# button-led-matrix-4x4.net
KiCad netlist of a schematic drawn in EAGLE
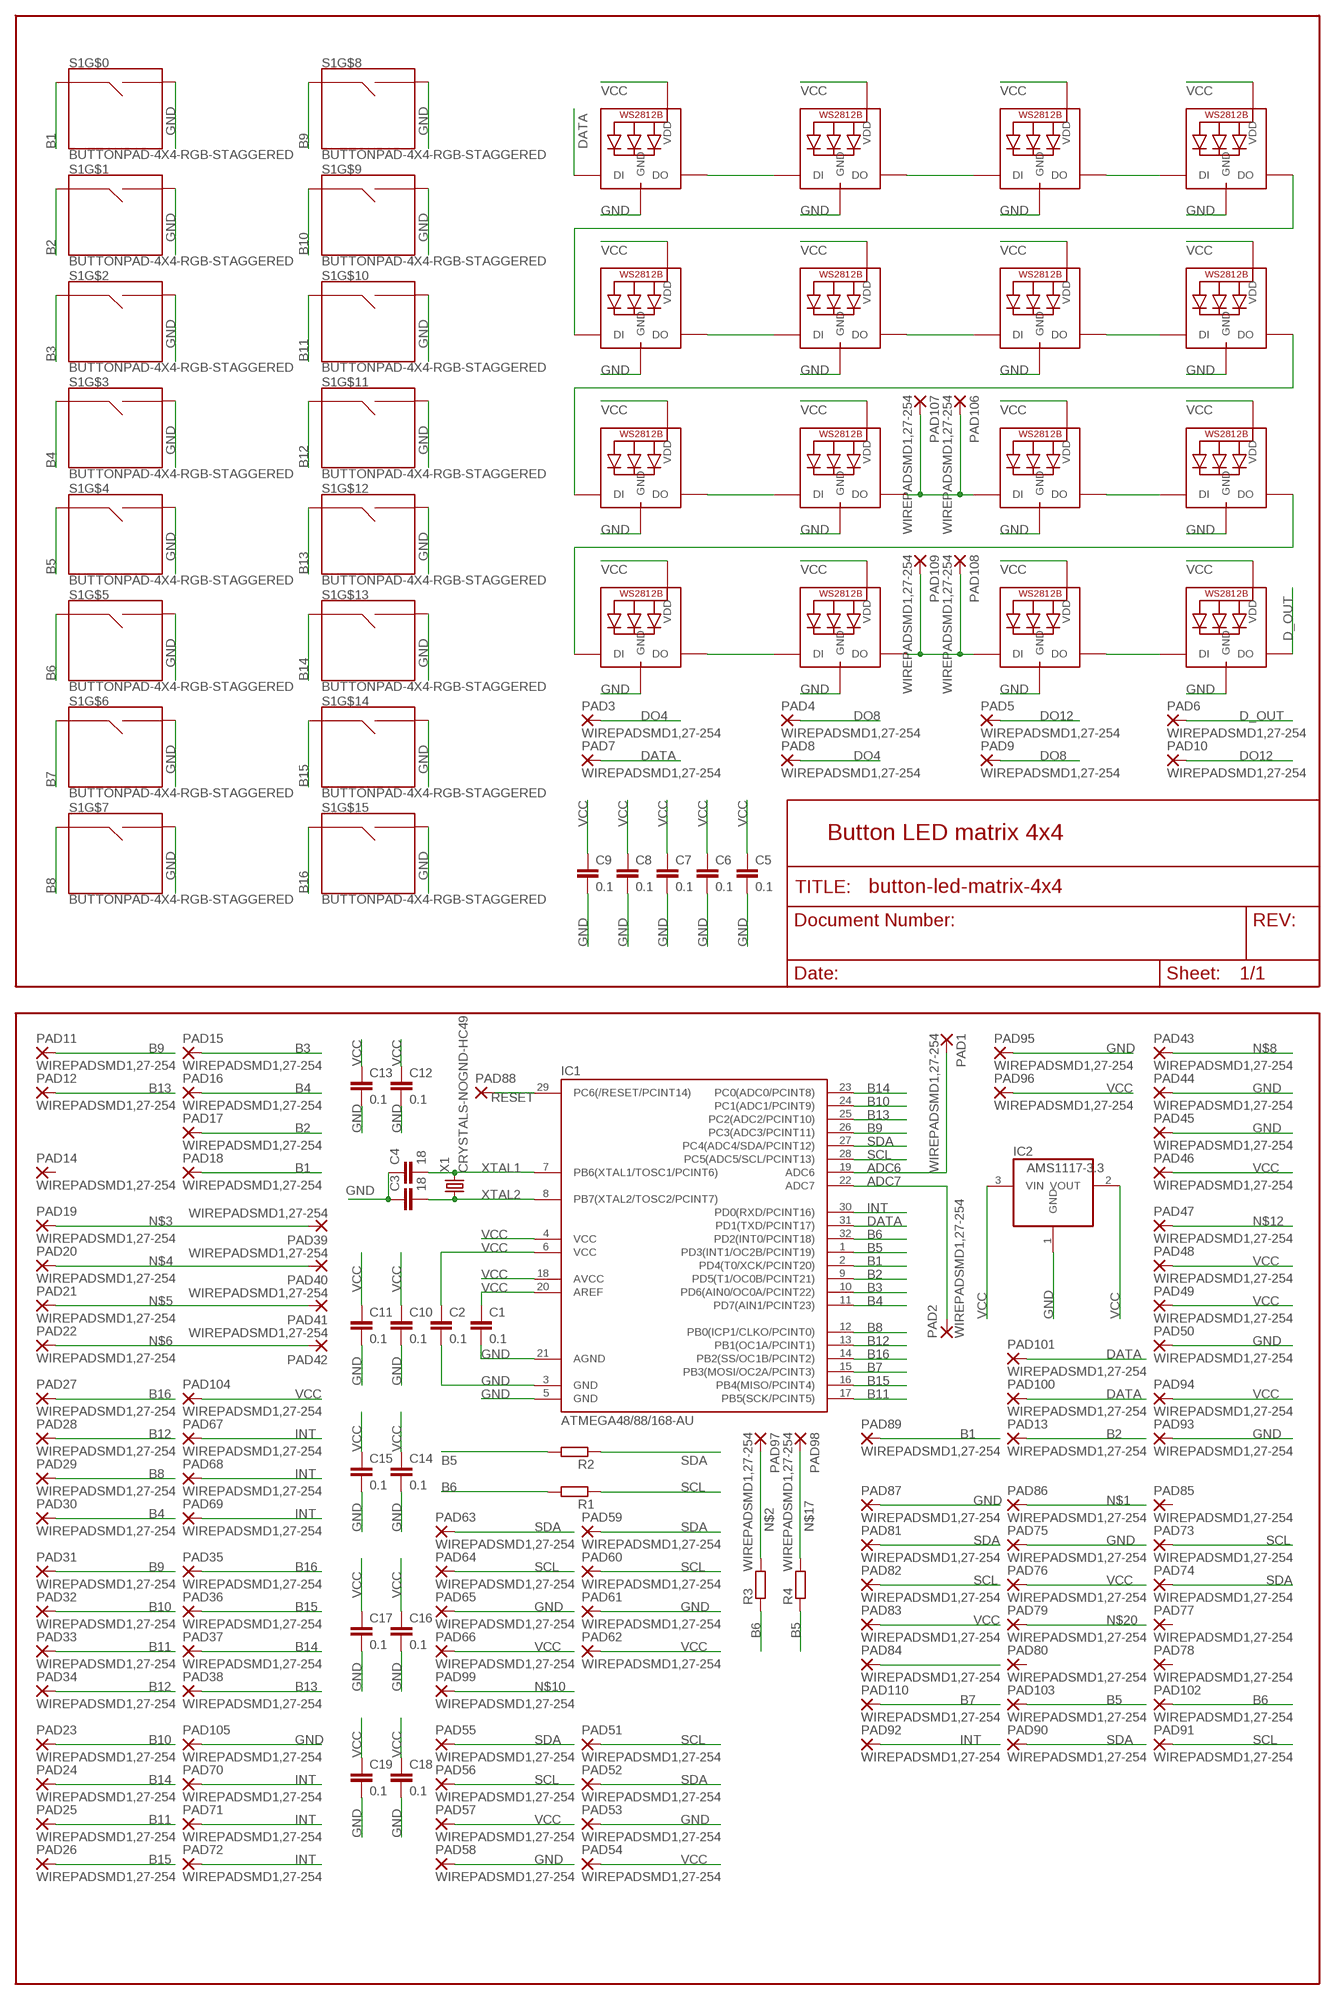
[diagram p0: schematic, sheet 1]

(export (version "E")
  (design (tool "Eeschema 10.0.6"))
  (components
    (comp (ref "C1")
      (value "0.1")
      (footprint "eagle-import:C0805")
      (libsource (lib "eagle-import") (part "C-EUC0805"))
    )
    (comp (ref "C2")
      (value "0.1")
      (footprint "eagle-import:C0805")
      (libsource (lib "eagle-import") (part "C-EUC0805"))
    )
    (comp (ref "C3")
      (value "18")
      (footprint "eagle-import:C0805")
      (libsource (lib "eagle-import") (part "C-EUC0805"))
    )
    (comp (ref "C4")
      (value "18")
      (footprint "eagle-import:C0805")
      (libsource (lib "eagle-import") (part "C-EUC0805"))
    )
    (comp (ref "C5")
      (value "0.1")
      (footprint "eagle-import:C0805")
      (libsource (lib "eagle-import") (part "C-EUC0805"))
    )
    (comp (ref "C6")
      (value "0.1")
      (footprint "eagle-import:C0805")
      (libsource (lib "eagle-import") (part "C-EUC0805"))
    )
    (comp (ref "C7")
      (value "0.1")
      (footprint "eagle-import:C0805")
      (libsource (lib "eagle-import") (part "C-EUC0805"))
    )
    (comp (ref "C8")
      (value "0.1")
      (footprint "eagle-import:C0805")
      (libsource (lib "eagle-import") (part "C-EUC0805"))
    )
    (comp (ref "C9")
      (value "0.1")
      (footprint "eagle-import:C0805")
      (libsource (lib "eagle-import") (part "C-EUC0805"))
    )
    (comp (ref "C10")
      (value "0.1")
      (footprint "eagle-import:C0805")
      (libsource (lib "eagle-import") (part "C-EUC0805"))
    )
    (comp (ref "C11")
      (value "0.1")
      (footprint "eagle-import:C0805")
      (libsource (lib "eagle-import") (part "C-EUC0805"))
    )
    (comp (ref "C12")
      (value "0.1")
      (footprint "eagle-import:C0805")
      (libsource (lib "eagle-import") (part "C-EUC0805"))
    )
    (comp (ref "C13")
      (value "0.1")
      (footprint "eagle-import:C0805")
      (libsource (lib "eagle-import") (part "C-EUC0805"))
    )
    (comp (ref "C14")
      (value "0.1")
      (footprint "eagle-import:C0805")
      (libsource (lib "eagle-import") (part "C-EUC0805"))
    )
    (comp (ref "C15")
      (value "0.1")
      (footprint "eagle-import:C0805")
      (libsource (lib "eagle-import") (part "C-EUC0805"))
    )
    (comp (ref "C16")
      (value "0.1")
      (footprint "eagle-import:C0805")
      (libsource (lib "eagle-import") (part "C-EUC0805"))
    )
    (comp (ref "C17")
      (value "0.1")
      (footprint "eagle-import:C0805")
      (libsource (lib "eagle-import") (part "C-EUC0805"))
    )
    (comp (ref "C18")
      (value "0.1")
      (footprint "eagle-import:C0805")
      (libsource (lib "eagle-import") (part "C-EUC0805"))
    )
    (comp (ref "C19")
      (value "0.1")
      (footprint "eagle-import:C0805")
      (libsource (lib "eagle-import") (part "C-EUC0805"))
    )
    (comp (ref "IC1")
      (value "ATMEGA48/88/168-AU")
      (footprint "eagle-import:TQFP32-08")
      (libsource (lib "eagle-import") (part "ATMEGA48/88/168-AU"))
    )
    (comp (ref "IC2")
      (value "AMS1117-3.3")
      (footprint "eagle-import:SOT223")
      (fields (field (name "MPN") "REG1117"))
      (libsource (lib "eagle-import") (part "REG1117"))
    )
    (comp (ref "LED1")
      (value "WS2812B_5050N")
      (footprint "eagle-import:WS2812B-NARROW")
      (libsource (lib "eagle-import") (part "WS2812B_5050N"))
    )
    (comp (ref "LED2")
      (value "WS2812B_5050N")
      (footprint "eagle-import:WS2812B-NARROW")
      (libsource (lib "eagle-import") (part "WS2812B_5050N"))
    )
    (comp (ref "LED3")
      (value "WS2812B_5050N")
      (footprint "eagle-import:WS2812B-NARROW")
      (libsource (lib "eagle-import") (part "WS2812B_5050N"))
    )
    (comp (ref "LED4")
      (value "WS2812B_5050N")
      (footprint "eagle-import:WS2812B-NARROW")
      (libsource (lib "eagle-import") (part "WS2812B_5050N"))
    )
    (comp (ref "LED5")
      (value "WS2812B_5050N")
      (footprint "eagle-import:WS2812B-NARROW")
      (libsource (lib "eagle-import") (part "WS2812B_5050N"))
    )
    (comp (ref "LED6")
      (value "WS2812B_5050N")
      (footprint "eagle-import:WS2812B-NARROW")
      (libsource (lib "eagle-import") (part "WS2812B_5050N"))
    )
    (comp (ref "LED7")
      (value "WS2812B_5050N")
      (footprint "eagle-import:WS2812B-NARROW")
      (libsource (lib "eagle-import") (part "WS2812B_5050N"))
    )
    (comp (ref "LED8")
      (value "WS2812B_5050N")
      (footprint "eagle-import:WS2812B-NARROW")
      (libsource (lib "eagle-import") (part "WS2812B_5050N"))
    )
    (comp (ref "LED9")
      (value "WS2812B_5050N")
      (footprint "eagle-import:WS2812B-NARROW")
      (libsource (lib "eagle-import") (part "WS2812B_5050N"))
    )
    (comp (ref "LED10")
      (value "WS2812B_5050N")
      (footprint "eagle-import:WS2812B-NARROW")
      (libsource (lib "eagle-import") (part "WS2812B_5050N"))
    )
    (comp (ref "LED11")
      (value "WS2812B_5050N")
      (footprint "eagle-import:WS2812B-NARROW")
      (libsource (lib "eagle-import") (part "WS2812B_5050N"))
    )
    (comp (ref "LED12")
      (value "WS2812B_5050N")
      (footprint "eagle-import:WS2812B-NARROW")
      (libsource (lib "eagle-import") (part "WS2812B_5050N"))
    )
    (comp (ref "LED13")
      (value "WS2812B_5050N")
      (footprint "eagle-import:WS2812B-NARROW")
      (libsource (lib "eagle-import") (part "WS2812B_5050N"))
    )
    (comp (ref "LED14")
      (value "WS2812B_5050N")
      (footprint "eagle-import:WS2812B-NARROW")
      (libsource (lib "eagle-import") (part "WS2812B_5050N"))
    )
    (comp (ref "LED15")
      (value "WS2812B_5050N")
      (footprint "eagle-import:WS2812B-NARROW")
      (libsource (lib "eagle-import") (part "WS2812B_5050N"))
    )
    (comp (ref "LED16")
      (value "WS2812B_5050N")
      (footprint "eagle-import:WS2812B-NARROW")
      (libsource (lib "eagle-import") (part "WS2812B_5050N"))
    )
    (comp (ref "PAD1")
      (value "WIREPADSMD1,27-254")
      (footprint "eagle-import:SMD1,27-2,54")
      (libsource (lib "eagle-import") (part "WIREPADSMD1,27-254"))
    )
    (comp (ref "PAD2")
      (value "WIREPADSMD1,27-254")
      (footprint "eagle-import:SMD1,27-2,54")
      (libsource (lib "eagle-import") (part "WIREPADSMD1,27-254"))
    )
    (comp (ref "PAD3")
      (value "WIREPADSMD1,27-254")
      (footprint "eagle-import:SMD1,27-2,54")
      (libsource (lib "eagle-import") (part "WIREPADSMD1,27-254"))
    )
    (comp (ref "PAD4")
      (value "WIREPADSMD1,27-254")
      (footprint "eagle-import:SMD1,27-2,54")
      (libsource (lib "eagle-import") (part "WIREPADSMD1,27-254"))
    )
    (comp (ref "PAD5")
      (value "WIREPADSMD1,27-254")
      (footprint "eagle-import:SMD1,27-2,54")
      (libsource (lib "eagle-import") (part "WIREPADSMD1,27-254"))
    )
    (comp (ref "PAD6")
      (value "WIREPADSMD1,27-254")
      (footprint "eagle-import:SMD1,27-2,54")
      (libsource (lib "eagle-import") (part "WIREPADSMD1,27-254"))
    )
    (comp (ref "PAD7")
      (value "WIREPADSMD1,27-254")
      (footprint "eagle-import:SMD1,27-2,54")
      (libsource (lib "eagle-import") (part "WIREPADSMD1,27-254"))
    )
    (comp (ref "PAD8")
      (value "WIREPADSMD1,27-254")
      (footprint "eagle-import:SMD1,27-2,54")
      (libsource (lib "eagle-import") (part "WIREPADSMD1,27-254"))
    )
    (comp (ref "PAD9")
      (value "WIREPADSMD1,27-254")
      (footprint "eagle-import:SMD1,27-2,54")
      (libsource (lib "eagle-import") (part "WIREPADSMD1,27-254"))
    )
    (comp (ref "PAD10")
      (value "WIREPADSMD1,27-254")
      (footprint "eagle-import:SMD1,27-2,54")
      (libsource (lib "eagle-import") (part "WIREPADSMD1,27-254"))
    )
    (comp (ref "PAD11")
      (value "WIREPADSMD1,27-254")
      (footprint "eagle-import:SMD1,27-2,54")
      (libsource (lib "eagle-import") (part "WIREPADSMD1,27-254"))
    )
    (comp (ref "PAD12")
      (value "WIREPADSMD1,27-254")
      (footprint "eagle-import:SMD1,27-2,54")
      (libsource (lib "eagle-import") (part "WIREPADSMD1,27-254"))
    )
    (comp (ref "PAD13")
      (value "WIREPADSMD1,27-254")
      (footprint "eagle-import:SMD1,27-2,54")
      (libsource (lib "eagle-import") (part "WIREPADSMD1,27-254"))
    )
    (comp (ref "PAD14")
      (value "WIREPADSMD1,27-254")
      (footprint "eagle-import:SMD1,27-2,54")
      (libsource (lib "eagle-import") (part "WIREPADSMD1,27-254"))
    )
    (comp (ref "PAD15")
      (value "WIREPADSMD1,27-254")
      (footprint "eagle-import:SMD1,27-2,54")
      (libsource (lib "eagle-import") (part "WIREPADSMD1,27-254"))
    )
    (comp (ref "PAD16")
      (value "WIREPADSMD1,27-254")
      (footprint "eagle-import:SMD1,27-2,54")
      (libsource (lib "eagle-import") (part "WIREPADSMD1,27-254"))
    )
    (comp (ref "PAD17")
      (value "WIREPADSMD1,27-254")
      (footprint "eagle-import:SMD1,27-2,54")
      (libsource (lib "eagle-import") (part "WIREPADSMD1,27-254"))
    )
    (comp (ref "PAD18")
      (value "WIREPADSMD1,27-254")
      (footprint "eagle-import:SMD1,27-2,54")
      (libsource (lib "eagle-import") (part "WIREPADSMD1,27-254"))
    )
    (comp (ref "PAD19")
      (value "WIREPADSMD1,27-254")
      (footprint "eagle-import:SMD1,27-2,54")
      (libsource (lib "eagle-import") (part "WIREPADSMD1,27-254"))
    )
    (comp (ref "PAD20")
      (value "WIREPADSMD1,27-254")
      (footprint "eagle-import:SMD1,27-2,54")
      (libsource (lib "eagle-import") (part "WIREPADSMD1,27-254"))
    )
    (comp (ref "PAD21")
      (value "WIREPADSMD1,27-254")
      (footprint "eagle-import:SMD1,27-2,54")
      (libsource (lib "eagle-import") (part "WIREPADSMD1,27-254"))
    )
    (comp (ref "PAD22")
      (value "WIREPADSMD1,27-254")
      (footprint "eagle-import:SMD1,27-2,54")
      (libsource (lib "eagle-import") (part "WIREPADSMD1,27-254"))
    )
    (comp (ref "PAD23")
      (value "WIREPADSMD1,27-254")
      (footprint "eagle-import:SMD1,27-2,54")
      (libsource (lib "eagle-import") (part "WIREPADSMD1,27-254"))
    )
    (comp (ref "PAD24")
      (value "WIREPADSMD1,27-254")
      (footprint "eagle-import:SMD1,27-2,54")
      (libsource (lib "eagle-import") (part "WIREPADSMD1,27-254"))
    )
    (comp (ref "PAD25")
      (value "WIREPADSMD1,27-254")
      (footprint "eagle-import:SMD1,27-2,54")
      (libsource (lib "eagle-import") (part "WIREPADSMD1,27-254"))
    )
    (comp (ref "PAD26")
      (value "WIREPADSMD1,27-254")
      (footprint "eagle-import:SMD1,27-2,54")
      (libsource (lib "eagle-import") (part "WIREPADSMD1,27-254"))
    )
    (comp (ref "PAD27")
      (value "WIREPADSMD1,27-254")
      (footprint "eagle-import:SMD1,27-2,54")
      (libsource (lib "eagle-import") (part "WIREPADSMD1,27-254"))
    )
    (comp (ref "PAD28")
      (value "WIREPADSMD1,27-254")
      (footprint "eagle-import:SMD1,27-2,54")
      (libsource (lib "eagle-import") (part "WIREPADSMD1,27-254"))
    )
    (comp (ref "PAD29")
      (value "WIREPADSMD1,27-254")
      (footprint "eagle-import:SMD1,27-2,54")
      (libsource (lib "eagle-import") (part "WIREPADSMD1,27-254"))
    )
    (comp (ref "PAD30")
      (value "WIREPADSMD1,27-254")
      (footprint "eagle-import:SMD1,27-2,54")
      (libsource (lib "eagle-import") (part "WIREPADSMD1,27-254"))
    )
    (comp (ref "PAD31")
      (value "WIREPADSMD1,27-254")
      (footprint "eagle-import:SMD1,27-2,54")
      (libsource (lib "eagle-import") (part "WIREPADSMD1,27-254"))
    )
    (comp (ref "PAD32")
      (value "WIREPADSMD1,27-254")
      (footprint "eagle-import:SMD1,27-2,54")
      (libsource (lib "eagle-import") (part "WIREPADSMD1,27-254"))
    )
    (comp (ref "PAD33")
      (value "WIREPADSMD1,27-254")
      (footprint "eagle-import:SMD1,27-2,54")
      (libsource (lib "eagle-import") (part "WIREPADSMD1,27-254"))
    )
    (comp (ref "PAD34")
      (value "WIREPADSMD1,27-254")
      (footprint "eagle-import:SMD1,27-2,54")
      (libsource (lib "eagle-import") (part "WIREPADSMD1,27-254"))
    )
    (comp (ref "PAD35")
      (value "WIREPADSMD1,27-254")
      (footprint "eagle-import:SMD1,27-2,54")
      (libsource (lib "eagle-import") (part "WIREPADSMD1,27-254"))
    )
    (comp (ref "PAD36")
      (value "WIREPADSMD1,27-254")
      (footprint "eagle-import:SMD1,27-2,54")
      (libsource (lib "eagle-import") (part "WIREPADSMD1,27-254"))
    )
    (comp (ref "PAD37")
      (value "WIREPADSMD1,27-254")
      (footprint "eagle-import:SMD1,27-2,54")
      (libsource (lib "eagle-import") (part "WIREPADSMD1,27-254"))
    )
    (comp (ref "PAD38")
      (value "WIREPADSMD1,27-254")
      (footprint "eagle-import:SMD1,27-2,54")
      (libsource (lib "eagle-import") (part "WIREPADSMD1,27-254"))
    )
    (comp (ref "PAD39")
      (value "WIREPADSMD1,27-254")
      (footprint "eagle-import:SMD1,27-2,54")
      (libsource (lib "eagle-import") (part "WIREPADSMD1,27-254"))
    )
    (comp (ref "PAD40")
      (value "WIREPADSMD1,27-254")
      (footprint "eagle-import:SMD1,27-2,54")
      (libsource (lib "eagle-import") (part "WIREPADSMD1,27-254"))
    )
    (comp (ref "PAD41")
      (value "WIREPADSMD1,27-254")
      (footprint "eagle-import:SMD1,27-2,54")
      (libsource (lib "eagle-import") (part "WIREPADSMD1,27-254"))
    )
    (comp (ref "PAD42")
      (value "WIREPADSMD1,27-254")
      (footprint "eagle-import:SMD1,27-2,54")
      (libsource (lib "eagle-import") (part "WIREPADSMD1,27-254"))
    )
    (comp (ref "PAD43")
      (value "WIREPADSMD1,27-254")
      (footprint "eagle-import:SMD1,27-2,54")
      (libsource (lib "eagle-import") (part "WIREPADSMD1,27-254"))
    )
    (comp (ref "PAD44")
      (value "WIREPADSMD1,27-254")
      (footprint "eagle-import:SMD1,27-2,54")
      (libsource (lib "eagle-import") (part "WIREPADSMD1,27-254"))
    )
    (comp (ref "PAD45")
      (value "WIREPADSMD1,27-254")
      (footprint "eagle-import:SMD1,27-2,54")
      (libsource (lib "eagle-import") (part "WIREPADSMD1,27-254"))
    )
    (comp (ref "PAD46")
      (value "WIREPADSMD1,27-254")
      (footprint "eagle-import:SMD1,27-2,54")
      (libsource (lib "eagle-import") (part "WIREPADSMD1,27-254"))
    )
    (comp (ref "PAD47")
      (value "WIREPADSMD1,27-254")
      (footprint "eagle-import:SMD1,27-2,54")
      (libsource (lib "eagle-import") (part "WIREPADSMD1,27-254"))
    )
    (comp (ref "PAD48")
      (value "WIREPADSMD1,27-254")
      (footprint "eagle-import:SMD1,27-2,54")
      (libsource (lib "eagle-import") (part "WIREPADSMD1,27-254"))
    )
    (comp (ref "PAD49")
      (value "WIREPADSMD1,27-254")
      (footprint "eagle-import:SMD1,27-2,54")
      (libsource (lib "eagle-import") (part "WIREPADSMD1,27-254"))
    )
    (comp (ref "PAD50")
      (value "WIREPADSMD1,27-254")
      (footprint "eagle-import:SMD1,27-2,54")
      (libsource (lib "eagle-import") (part "WIREPADSMD1,27-254"))
    )
    (comp (ref "PAD51")
      (value "WIREPADSMD1,27-254")
      (footprint "eagle-import:SMD1,27-2,54")
      (libsource (lib "eagle-import") (part "WIREPADSMD1,27-254"))
    )
    (comp (ref "PAD52")
      (value "WIREPADSMD1,27-254")
      (footprint "eagle-import:SMD1,27-2,54")
      (libsource (lib "eagle-import") (part "WIREPADSMD1,27-254"))
    )
    (comp (ref "PAD53")
      (value "WIREPADSMD1,27-254")
      (footprint "eagle-import:SMD1,27-2,54")
      (libsource (lib "eagle-import") (part "WIREPADSMD1,27-254"))
    )
    (comp (ref "PAD54")
      (value "WIREPADSMD1,27-254")
      (footprint "eagle-import:SMD1,27-2,54")
      (libsource (lib "eagle-import") (part "WIREPADSMD1,27-254"))
    )
    (comp (ref "PAD55")
      (value "WIREPADSMD1,27-254")
      (footprint "eagle-import:SMD1,27-2,54")
      (libsource (lib "eagle-import") (part "WIREPADSMD1,27-254"))
    )
    (comp (ref "PAD56")
      (value "WIREPADSMD1,27-254")
      (footprint "eagle-import:SMD1,27-2,54")
      (libsource (lib "eagle-import") (part "WIREPADSMD1,27-254"))
    )
    (comp (ref "PAD57")
      (value "WIREPADSMD1,27-254")
      (footprint "eagle-import:SMD1,27-2,54")
      (libsource (lib "eagle-import") (part "WIREPADSMD1,27-254"))
    )
    (comp (ref "PAD58")
      (value "WIREPADSMD1,27-254")
      (footprint "eagle-import:SMD1,27-2,54")
      (libsource (lib "eagle-import") (part "WIREPADSMD1,27-254"))
    )
    (comp (ref "PAD59")
      (value "WIREPADSMD1,27-254")
      (footprint "eagle-import:SMD1,27-2,54")
      (libsource (lib "eagle-import") (part "WIREPADSMD1,27-254"))
    )
    (comp (ref "PAD60")
      (value "WIREPADSMD1,27-254")
      (footprint "eagle-import:SMD1,27-2,54")
      (libsource (lib "eagle-import") (part "WIREPADSMD1,27-254"))
    )
    (comp (ref "PAD61")
      (value "WIREPADSMD1,27-254")
      (footprint "eagle-import:SMD1,27-2,54")
      (libsource (lib "eagle-import") (part "WIREPADSMD1,27-254"))
    )
    (comp (ref "PAD62")
      (value "WIREPADSMD1,27-254")
      (footprint "eagle-import:SMD1,27-2,54")
      (libsource (lib "eagle-import") (part "WIREPADSMD1,27-254"))
    )
    (comp (ref "PAD63")
      (value "WIREPADSMD1,27-254")
      (footprint "eagle-import:SMD1,27-2,54")
      (libsource (lib "eagle-import") (part "WIREPADSMD1,27-254"))
    )
    (comp (ref "PAD64")
      (value "WIREPADSMD1,27-254")
      (footprint "eagle-import:SMD1,27-2,54")
      (libsource (lib "eagle-import") (part "WIREPADSMD1,27-254"))
    )
    (comp (ref "PAD65")
      (value "WIREPADSMD1,27-254")
      (footprint "eagle-import:SMD1,27-2,54")
      (libsource (lib "eagle-import") (part "WIREPADSMD1,27-254"))
    )
    (comp (ref "PAD66")
      (value "WIREPADSMD1,27-254")
      (footprint "eagle-import:SMD1,27-2,54")
      (libsource (lib "eagle-import") (part "WIREPADSMD1,27-254"))
    )
    (comp (ref "PAD67")
      (value "WIREPADSMD1,27-254")
      (footprint "eagle-import:SMD1,27-2,54")
      (libsource (lib "eagle-import") (part "WIREPADSMD1,27-254"))
    )
    (comp (ref "PAD68")
      (value "WIREPADSMD1,27-254")
      (footprint "eagle-import:SMD1,27-2,54")
      (libsource (lib "eagle-import") (part "WIREPADSMD1,27-254"))
    )
    (comp (ref "PAD69")
      (value "WIREPADSMD1,27-254")
      (footprint "eagle-import:SMD1,27-2,54")
      (libsource (lib "eagle-import") (part "WIREPADSMD1,27-254"))
    )
    (comp (ref "PAD70")
      (value "WIREPADSMD1,27-254")
      (footprint "eagle-import:SMD1,27-2,54")
      (libsource (lib "eagle-import") (part "WIREPADSMD1,27-254"))
    )
    (comp (ref "PAD71")
      (value "WIREPADSMD1,27-254")
      (footprint "eagle-import:SMD1,27-2,54")
      (libsource (lib "eagle-import") (part "WIREPADSMD1,27-254"))
    )
    (comp (ref "PAD72")
      (value "WIREPADSMD1,27-254")
      (footprint "eagle-import:SMD1,27-2,54")
      (libsource (lib "eagle-import") (part "WIREPADSMD1,27-254"))
    )
    (comp (ref "PAD73")
      (value "WIREPADSMD1,27-254")
      (footprint "eagle-import:SMD1,27-2,54")
      (libsource (lib "eagle-import") (part "WIREPADSMD1,27-254"))
    )
    (comp (ref "PAD74")
      (value "WIREPADSMD1,27-254")
      (footprint "eagle-import:SMD1,27-2,54")
      (libsource (lib "eagle-import") (part "WIREPADSMD1,27-254"))
    )
    (comp (ref "PAD75")
      (value "WIREPADSMD1,27-254")
      (footprint "eagle-import:SMD1,27-2,54")
      (libsource (lib "eagle-import") (part "WIREPADSMD1,27-254"))
    )
    (comp (ref "PAD76")
      (value "WIREPADSMD1,27-254")
      (footprint "eagle-import:SMD1,27-2,54")
      (libsource (lib "eagle-import") (part "WIREPADSMD1,27-254"))
    )
    (comp (ref "PAD77")
      (value "WIREPADSMD1,27-254")
      (footprint "eagle-import:SMD1,27-2,54")
      (libsource (lib "eagle-import") (part "WIREPADSMD1,27-254"))
    )
    (comp (ref "PAD78")
      (value "WIREPADSMD1,27-254")
      (footprint "eagle-import:SMD1,27-2,54")
      (libsource (lib "eagle-import") (part "WIREPADSMD1,27-254"))
    )
    (comp (ref "PAD79")
      (value "WIREPADSMD1,27-254")
      (footprint "eagle-import:SMD1,27-2,54")
      (libsource (lib "eagle-import") (part "WIREPADSMD1,27-254"))
    )
    (comp (ref "PAD80")
      (value "WIREPADSMD1,27-254")
      (footprint "eagle-import:SMD1,27-2,54")
      (libsource (lib "eagle-import") (part "WIREPADSMD1,27-254"))
    )
    (comp (ref "PAD81")
      (value "WIREPADSMD1,27-254")
      (footprint "eagle-import:SMD1,27-2,54")
      (libsource (lib "eagle-import") (part "WIREPADSMD1,27-254"))
    )
    (comp (ref "PAD82")
      (value "WIREPADSMD1,27-254")
      (footprint "eagle-import:SMD1,27-2,54")
      (libsource (lib "eagle-import") (part "WIREPADSMD1,27-254"))
    )
    (comp (ref "PAD83")
      (value "WIREPADSMD1,27-254")
      (footprint "eagle-import:SMD1,27-2,54")
      (libsource (lib "eagle-import") (part "WIREPADSMD1,27-254"))
    )
    (comp (ref "PAD84")
      (value "WIREPADSMD1,27-254")
      (footprint "eagle-import:SMD1,27-2,54")
      (libsource (lib "eagle-import") (part "WIREPADSMD1,27-254"))
    )
    (comp (ref "PAD85")
      (value "WIREPADSMD1,27-254")
      (footprint "eagle-import:SMD1,27-2,54")
      (libsource (lib "eagle-import") (part "WIREPADSMD1,27-254"))
    )
    (comp (ref "PAD86")
      (value "WIREPADSMD1,27-254")
      (footprint "eagle-import:SMD1,27-2,54")
      (libsource (lib "eagle-import") (part "WIREPADSMD1,27-254"))
    )
    (comp (ref "PAD87")
      (value "WIREPADSMD1,27-254")
      (footprint "eagle-import:SMD1,27-2,54")
      (libsource (lib "eagle-import") (part "WIREPADSMD1,27-254"))
    )
    (comp (ref "PAD88")
      (value "1,6/0,8")
      (footprint "eagle-import:1,6_0,8")
      (libsource (lib "eagle-import") (part "1,6/0,8"))
    )
    (comp (ref "PAD89")
      (value "WIREPADSMD1,27-254")
      (footprint "eagle-import:SMD1,27-2,54")
      (libsource (lib "eagle-import") (part "WIREPADSMD1,27-254"))
    )
    (comp (ref "PAD90")
      (value "WIREPADSMD1,27-254")
      (footprint "eagle-import:SMD1,27-2,54")
      (libsource (lib "eagle-import") (part "WIREPADSMD1,27-254"))
    )
    (comp (ref "PAD91")
      (value "WIREPADSMD1,27-254")
      (footprint "eagle-import:SMD1,27-2,54")
      (libsource (lib "eagle-import") (part "WIREPADSMD1,27-254"))
    )
    (comp (ref "PAD92")
      (value "WIREPADSMD1,27-254")
      (footprint "eagle-import:SMD1,27-2,54")
      (libsource (lib "eagle-import") (part "WIREPADSMD1,27-254"))
    )
    (comp (ref "PAD93")
      (value "WIREPADSMD1,27-254")
      (footprint "eagle-import:SMD1,27-2,54")
      (libsource (lib "eagle-import") (part "WIREPADSMD1,27-254"))
    )
    (comp (ref "PAD94")
      (value "WIREPADSMD1,27-254")
      (footprint "eagle-import:SMD1,27-2,54")
      (libsource (lib "eagle-import") (part "WIREPADSMD1,27-254"))
    )
    (comp (ref "PAD95")
      (value "WIREPADSMD1,27-254")
      (footprint "eagle-import:SMD1,27-2,54")
      (libsource (lib "eagle-import") (part "WIREPADSMD1,27-254"))
    )
    (comp (ref "PAD96")
      (value "WIREPADSMD1,27-254")
      (footprint "eagle-import:SMD1,27-2,54")
      (libsource (lib "eagle-import") (part "WIREPADSMD1,27-254"))
    )
    (comp (ref "PAD97")
      (value "WIREPADSMD1,27-254")
      (footprint "eagle-import:SMD1,27-2,54")
      (libsource (lib "eagle-import") (part "WIREPADSMD1,27-254"))
    )
    (comp (ref "PAD98")
      (value "WIREPADSMD1,27-254")
      (footprint "eagle-import:SMD1,27-2,54")
      (libsource (lib "eagle-import") (part "WIREPADSMD1,27-254"))
    )
    (comp (ref "PAD99")
      (value "WIREPADSMD1,27-254")
      (footprint "eagle-import:SMD1,27-2,54")
      (libsource (lib "eagle-import") (part "WIREPADSMD1,27-254"))
    )
    (comp (ref "PAD100")
      (value "WIREPADSMD1,27-254")
      (footprint "eagle-import:SMD1,27-2,54")
      (libsource (lib "eagle-import") (part "WIREPADSMD1,27-254"))
    )
    (comp (ref "PAD101")
      (value "WIREPADSMD1,27-254")
      (footprint "eagle-import:SMD1,27-2,54")
      (libsource (lib "eagle-import") (part "WIREPADSMD1,27-254"))
    )
    (comp (ref "PAD102")
      (value "WIREPADSMD1,27-254")
      (footprint "eagle-import:SMD1,27-2,54")
      (libsource (lib "eagle-import") (part "WIREPADSMD1,27-254"))
    )
    (comp (ref "PAD103")
      (value "WIREPADSMD1,27-254")
      (footprint "eagle-import:SMD1,27-2,54")
      (libsource (lib "eagle-import") (part "WIREPADSMD1,27-254"))
    )
    (comp (ref "PAD104")
      (value "WIREPADSMD1,27-254")
      (footprint "eagle-import:SMD1,27-2,54")
      (libsource (lib "eagle-import") (part "WIREPADSMD1,27-254"))
    )
    (comp (ref "PAD105")
      (value "WIREPADSMD1,27-254")
      (footprint "eagle-import:SMD1,27-2,54")
      (libsource (lib "eagle-import") (part "WIREPADSMD1,27-254"))
    )
    (comp (ref "PAD106")
      (value "WIREPADSMD1,27-254")
      (footprint "eagle-import:SMD1,27-2,54")
      (libsource (lib "eagle-import") (part "WIREPADSMD1,27-254"))
    )
    (comp (ref "PAD107")
      (value "WIREPADSMD1,27-254")
      (footprint "eagle-import:SMD1,27-2,54")
      (libsource (lib "eagle-import") (part "WIREPADSMD1,27-254"))
    )
    (comp (ref "PAD108")
      (value "WIREPADSMD1,27-254")
      (footprint "eagle-import:SMD1,27-2,54")
      (libsource (lib "eagle-import") (part "WIREPADSMD1,27-254"))
    )
    (comp (ref "PAD109")
      (value "WIREPADSMD1,27-254")
      (footprint "eagle-import:SMD1,27-2,54")
      (libsource (lib "eagle-import") (part "WIREPADSMD1,27-254"))
    )
    (comp (ref "PAD110")
      (value "WIREPADSMD1,27-254")
      (footprint "eagle-import:SMD1,27-2,54")
      (libsource (lib "eagle-import") (part "WIREPADSMD1,27-254"))
    )
    (comp (ref "R1")
      (value "R-EU_R1206")
      (footprint "eagle-import:R1206")
      (libsource (lib "eagle-import") (part "R-EU_R1206"))
    )
    (comp (ref "R2")
      (value "R-EU_R1206")
      (footprint "eagle-import:R1206")
      (libsource (lib "eagle-import") (part "R-EU_R1206"))
    )
    (comp (ref "R3")
      (value "R-EU_R0805")
      (footprint "eagle-import:R0805")
      (libsource (lib "eagle-import") (part "R-EU_R0805"))
    )
    (comp (ref "R4")
      (value "R-EU_R0805")
      (footprint "eagle-import:R0805")
      (libsource (lib "eagle-import") (part "R-EU_R0805"))
    )
    (comp (ref "S1")
      (value "BUTTONPAD-4X4-RGB-STAGGERED")
      (footprint "eagle-import:BUTTONPAD-4X4-STAGGERED")
      (libsource (lib "eagle-import") (part "BUTTONPAD-4X4-RGB-STAGGERED"))
    )
    (comp (ref "X1")
      (value "CRYSTALS-NOGND-HC49")
      (footprint "eagle-import:HC49")
      (libsource (lib "eagle-import") (part "CRYSTALS-NOGND-HC49"))
    )
  )
  (nets
    (net (code "1") (name "/ADC6") (class "Default")
      (node (ref "IC1") (pin "19") (pinfunction "ADC6_19") (pintype "passive"))
      (node (ref "PAD1") (pin "1") (pinfunction "P_1") (pintype "passive"))
    )
    (net (code "2") (name "/ADC7") (class "Default")
      (node (ref "IC1") (pin "22") (pinfunction "ADC7_22") (pintype "passive"))
      (node (ref "PAD2") (pin "1") (pinfunction "P_1") (pintype "passive"))
    )
    (net (code "3") (name "/B1") (class "Default")
      (node (ref "IC1") (pin "2") (pinfunction "PD4(T0/XCK/PCINT20)_2") (pintype "bidirectional"))
      (node (ref "PAD18") (pin "1") (pinfunction "P_1") (pintype "passive"))
      (node (ref "PAD89") (pin "1") (pinfunction "P_1") (pintype "passive"))
      (node (ref "S1") (pin "SIG0") (pinfunction "SIG1_SIG0") (pintype "bidirectional"))
    )
    (net (code "4") (name "/B2") (class "Default")
      (node (ref "IC1") (pin "9") (pinfunction "PD5(T1/OC0B/PCINT21)_9") (pintype "bidirectional"))
      (node (ref "PAD13") (pin "1") (pinfunction "P_1") (pintype "passive"))
      (node (ref "PAD17") (pin "1") (pinfunction "P_1") (pintype "passive"))
      (node (ref "S1") (pin "SIG2") (pinfunction "SIG1_SIG2") (pintype "bidirectional"))
    )
    (net (code "5") (name "/B3") (class "Default")
      (node (ref "IC1") (pin "10") (pinfunction "PD6(AIN0/OC0A/PCINT22)_10") (pintype "bidirectional"))
      (node (ref "PAD15") (pin "1") (pinfunction "P_1") (pintype "passive"))
      (node (ref "S1") (pin "SIG4") (pinfunction "SIG1_SIG4") (pintype "bidirectional"))
    )
    (net (code "6") (name "/B4") (class "Default")
      (node (ref "IC1") (pin "11") (pinfunction "PD7(AIN1/PCINT23)_11") (pintype "bidirectional"))
      (node (ref "PAD16") (pin "1") (pinfunction "P_1") (pintype "passive"))
      (node (ref "PAD30") (pin "1") (pinfunction "P_1") (pintype "passive"))
      (node (ref "S1") (pin "SIG6") (pinfunction "SIG1_SIG6") (pintype "bidirectional"))
    )
    (net (code "7") (name "/B5") (class "Default")
      (node (ref "IC1") (pin "1") (pinfunction "PD3(INT1/OC2B/PCINT19)_1") (pintype "bidirectional"))
      (node (ref "PAD103") (pin "1") (pinfunction "P_1") (pintype "passive"))
      (node (ref "R2") (pin "2") (pinfunction "2_2") (pintype "passive"))
      (node (ref "R4") (pin "1") (pinfunction "1_1") (pintype "passive"))
      (node (ref "S1") (pin "SIG8") (pinfunction "SIG1_SIG8") (pintype "bidirectional"))
    )
    (net (code "8") (name "/B6") (class "Default")
      (node (ref "IC1") (pin "32") (pinfunction "PD2(INT0/PCINT18)_32") (pintype "bidirectional"))
      (node (ref "PAD102") (pin "1") (pinfunction "P_1") (pintype "passive"))
      (node (ref "R1") (pin "2") (pinfunction "2_2") (pintype "passive"))
      (node (ref "R3") (pin "1") (pinfunction "1_1") (pintype "passive"))
      (node (ref "S1") (pin "SIG10") (pinfunction "SIG1_SIG10") (pintype "bidirectional"))
    )
    (net (code "9") (name "/B7") (class "Default")
      (node (ref "IC1") (pin "15") (pinfunction "PB3(MOSI/OC2A/PCINT3)_15") (pintype "bidirectional"))
      (node (ref "PAD110") (pin "1") (pinfunction "P_1") (pintype "passive"))
      (node (ref "S1") (pin "SIG12") (pinfunction "SIG1_SIG12") (pintype "bidirectional"))
    )
    (net (code "10") (name "/B8") (class "Default")
      (node (ref "IC1") (pin "12") (pinfunction "PB0(ICP1/CLKO/PCINT0)_12") (pintype "bidirectional"))
      (node (ref "PAD29") (pin "1") (pinfunction "P_1") (pintype "passive"))
      (node (ref "S1") (pin "SIG14") (pinfunction "SIG1_SIG14") (pintype "bidirectional"))
    )
    (net (code "11") (name "/B9") (class "Default")
      (node (ref "IC1") (pin "26") (pinfunction "PC3(ADC3/PCINT11)_26") (pintype "bidirectional"))
      (node (ref "PAD11") (pin "1") (pinfunction "P_1") (pintype "passive"))
      (node (ref "PAD31") (pin "1") (pinfunction "P_1") (pintype "passive"))
      (node (ref "S1") (pin "SIG16") (pinfunction "SIG1_SIG16") (pintype "bidirectional"))
    )
    (net (code "12") (name "/B10") (class "Default")
      (node (ref "IC1") (pin "24") (pinfunction "PC1(ADC1/PCINT9)_24") (pintype "bidirectional"))
      (node (ref "PAD23") (pin "1") (pinfunction "P_1") (pintype "passive"))
      (node (ref "PAD32") (pin "1") (pinfunction "P_1") (pintype "passive"))
      (node (ref "S1") (pin "SIG18") (pinfunction "SIG1_SIG18") (pintype "bidirectional"))
    )
    (net (code "13") (name "/B11") (class "Default")
      (node (ref "IC1") (pin "17") (pinfunction "PB5(SCK/PCINT5)_17") (pintype "bidirectional"))
      (node (ref "PAD25") (pin "1") (pinfunction "P_1") (pintype "passive"))
      (node (ref "PAD33") (pin "1") (pinfunction "P_1") (pintype "passive"))
      (node (ref "S1") (pin "SIG20") (pinfunction "SIG1_SIG20") (pintype "bidirectional"))
    )
    (net (code "14") (name "/B12") (class "Default")
      (node (ref "IC1") (pin "13") (pinfunction "PB1(OC1A/PCINT1)_13") (pintype "bidirectional"))
      (node (ref "PAD28") (pin "1") (pinfunction "P_1") (pintype "passive"))
      (node (ref "PAD34") (pin "1") (pinfunction "P_1") (pintype "passive"))
      (node (ref "S1") (pin "SIG22") (pinfunction "SIG1_SIG22") (pintype "bidirectional"))
    )
    (net (code "15") (name "/B13") (class "Default")
      (node (ref "IC1") (pin "25") (pinfunction "PC2(ADC2/PCINT10)_25") (pintype "bidirectional"))
      (node (ref "PAD12") (pin "1") (pinfunction "P_1") (pintype "passive"))
      (node (ref "PAD38") (pin "1") (pinfunction "P_1") (pintype "passive"))
      (node (ref "S1") (pin "SIG24") (pinfunction "SIG1_SIG24") (pintype "bidirectional"))
    )
    (net (code "16") (name "/B14") (class "Default")
      (node (ref "IC1") (pin "23") (pinfunction "PC0(ADC0/PCINT8)_23") (pintype "bidirectional"))
      (node (ref "PAD24") (pin "1") (pinfunction "P_1") (pintype "passive"))
      (node (ref "PAD37") (pin "1") (pinfunction "P_1") (pintype "passive"))
      (node (ref "S1") (pin "SIG26") (pinfunction "SIG1_SIG26") (pintype "bidirectional"))
    )
    (net (code "17") (name "/B15") (class "Default")
      (node (ref "IC1") (pin "16") (pinfunction "PB4(MISO/PCINT4)_16") (pintype "bidirectional"))
      (node (ref "PAD26") (pin "1") (pinfunction "P_1") (pintype "passive"))
      (node (ref "PAD36") (pin "1") (pinfunction "P_1") (pintype "passive"))
      (node (ref "S1") (pin "SIG28") (pinfunction "SIG1_SIG28") (pintype "bidirectional"))
    )
    (net (code "18") (name "/B16") (class "Default")
      (node (ref "IC1") (pin "14") (pinfunction "PB2(SS/OC1B/PCINT2)_14") (pintype "bidirectional"))
      (node (ref "PAD27") (pin "1") (pinfunction "P_1") (pintype "passive"))
      (node (ref "PAD35") (pin "1") (pinfunction "P_1") (pintype "passive"))
      (node (ref "S1") (pin "SIG30") (pinfunction "SIG1_SIG30") (pintype "bidirectional"))
    )
    (net (code "19") (name "/DATA") (class "Default")
      (node (ref "IC1") (pin "31") (pinfunction "PD1(TXD/PCINT17)_31") (pintype "bidirectional"))
      (node (ref "LED1") (pin "4-DIN") (pinfunction "DI_4-DIN") (pintype "input"))
      (node (ref "PAD100") (pin "1") (pinfunction "P_1") (pintype "passive"))
      (node (ref "PAD101") (pin "1") (pinfunction "P_1") (pintype "passive"))
      (node (ref "PAD7") (pin "1") (pinfunction "P_1") (pintype "passive"))
    )
    (net (code "20") (name "/DO4") (class "Default")
      (node (ref "LED4") (pin "2-DOUT") (pinfunction "DO_2-DOUT") (pintype "output"))
      (node (ref "LED5") (pin "4-DIN") (pinfunction "DI_4-DIN") (pintype "input"))
      (node (ref "PAD3") (pin "1") (pinfunction "P_1") (pintype "passive"))
      (node (ref "PAD8") (pin "1") (pinfunction "P_1") (pintype "passive"))
    )
    (net (code "21") (name "/DO8") (class "Default")
      (node (ref "LED8") (pin "2-DOUT") (pinfunction "DO_2-DOUT") (pintype "output"))
      (node (ref "LED9") (pin "4-DIN") (pinfunction "DI_4-DIN") (pintype "input"))
      (node (ref "PAD4") (pin "1") (pinfunction "P_1") (pintype "passive"))
      (node (ref "PAD9") (pin "1") (pinfunction "P_1") (pintype "passive"))
    )
    (net (code "22") (name "/DO12") (class "Default")
      (node (ref "LED12") (pin "2-DOUT") (pinfunction "DO_2-DOUT") (pintype "output"))
      (node (ref "LED13") (pin "4-DIN") (pinfunction "DI_4-DIN") (pintype "input"))
      (node (ref "PAD10") (pin "1") (pinfunction "P_1") (pintype "passive"))
      (node (ref "PAD5") (pin "1") (pinfunction "P_1") (pintype "passive"))
    )
    (net (code "23") (name "/D_OUT") (class "Default")
      (node (ref "LED16") (pin "2-DOUT") (pinfunction "DO_2-DOUT") (pintype "output"))
      (node (ref "PAD6") (pin "1") (pinfunction "P_1") (pintype "passive"))
    )
    (net (code "24") (name "/GND") (class "Default")
      (node (ref "C1") (pin "2") (pinfunction "2_2") (pintype "passive"))
      (node (ref "C10") (pin "2") (pinfunction "2_2") (pintype "passive"))
      (node (ref "C11") (pin "2") (pinfunction "2_2") (pintype "passive"))
      (node (ref "C12") (pin "2") (pinfunction "2_2") (pintype "passive"))
      (node (ref "C13") (pin "2") (pinfunction "2_2") (pintype "passive"))
      (node (ref "C14") (pin "2") (pinfunction "2_2") (pintype "passive"))
      (node (ref "C15") (pin "2") (pinfunction "2_2") (pintype "passive"))
      (node (ref "C16") (pin "2") (pinfunction "2_2") (pintype "passive"))
      (node (ref "C17") (pin "2") (pinfunction "2_2") (pintype "passive"))
      (node (ref "C18") (pin "2") (pinfunction "2_2") (pintype "passive"))
      (node (ref "C19") (pin "2") (pinfunction "2_2") (pintype "passive"))
      (node (ref "C2") (pin "2") (pinfunction "2_2") (pintype "passive"))
      (node (ref "C3") (pin "1") (pinfunction "1_1") (pintype "passive"))
      (node (ref "C4") (pin "1") (pinfunction "1_1") (pintype "passive"))
      (node (ref "C5") (pin "2") (pinfunction "2_2") (pintype "passive"))
      (node (ref "C6") (pin "2") (pinfunction "2_2") (pintype "passive"))
      (node (ref "C7") (pin "2") (pinfunction "2_2") (pintype "passive"))
      (node (ref "C8") (pin "2") (pinfunction "2_2") (pintype "passive"))
      (node (ref "C9") (pin "2") (pinfunction "2_2") (pintype "passive"))
      (node (ref "IC1") (pin "21") (pinfunction "AGND_21") (pintype "power_in"))
      (node (ref "IC1") (pin "3") (pinfunction "GND_3") (pintype "power_in"))
      (node (ref "IC1") (pin "5") (pinfunction "GND_5") (pintype "power_in"))
      (node (ref "IC2") (pin "1") (pinfunction "GND_1") (pintype "power_in"))
      (node (ref "LED1") (pin "3-GND") (pinfunction "GND_3-GND") (pintype "power_in"))
      (node (ref "LED10") (pin "3-GND") (pinfunction "GND_3-GND") (pintype "power_in"))
      (node (ref "LED11") (pin "3-GND") (pinfunction "GND_3-GND") (pintype "power_in"))
      (node (ref "LED12") (pin "3-GND") (pinfunction "GND_3-GND") (pintype "power_in"))
      (node (ref "LED13") (pin "3-GND") (pinfunction "GND_3-GND") (pintype "power_in"))
      (node (ref "LED14") (pin "3-GND") (pinfunction "GND_3-GND") (pintype "power_in"))
      (node (ref "LED15") (pin "3-GND") (pinfunction "GND_3-GND") (pintype "power_in"))
      (node (ref "LED16") (pin "3-GND") (pinfunction "GND_3-GND") (pintype "power_in"))
      (node (ref "LED2") (pin "3-GND") (pinfunction "GND_3-GND") (pintype "power_in"))
      (node (ref "LED3") (pin "3-GND") (pinfunction "GND_3-GND") (pintype "power_in"))
      (node (ref "LED4") (pin "3-GND") (pinfunction "GND_3-GND") (pintype "power_in"))
      (node (ref "LED5") (pin "3-GND") (pinfunction "GND_3-GND") (pintype "power_in"))
      (node (ref "LED6") (pin "3-GND") (pinfunction "GND_3-GND") (pintype "power_in"))
      (node (ref "LED7") (pin "3-GND") (pinfunction "GND_3-GND") (pintype "power_in"))
      (node (ref "LED8") (pin "3-GND") (pinfunction "GND_3-GND") (pintype "power_in"))
      (node (ref "LED9") (pin "3-GND") (pinfunction "GND_3-GND") (pintype "power_in"))
      (node (ref "PAD105") (pin "1") (pinfunction "P_1") (pintype "passive"))
      (node (ref "PAD44") (pin "1") (pinfunction "P_1") (pintype "passive"))
      (node (ref "PAD45") (pin "1") (pinfunction "P_1") (pintype "passive"))
      (node (ref "PAD50") (pin "1") (pinfunction "P_1") (pintype "passive"))
      (node (ref "PAD53") (pin "1") (pinfunction "P_1") (pintype "passive"))
      (node (ref "PAD58") (pin "1") (pinfunction "P_1") (pintype "passive"))
      (node (ref "PAD61") (pin "1") (pinfunction "P_1") (pintype "passive"))
      (node (ref "PAD65") (pin "1") (pinfunction "P_1") (pintype "passive"))
      (node (ref "PAD75") (pin "1") (pinfunction "P_1") (pintype "passive"))
      (node (ref "PAD87") (pin "1") (pinfunction "P_1") (pintype "passive"))
      (node (ref "PAD93") (pin "1") (pinfunction "P_1") (pintype "passive"))
      (node (ref "PAD95") (pin "1") (pinfunction "P_1") (pintype "passive"))
      (node (ref "S1") (pin "SIG1") (pinfunction "SIG2_SIG1") (pintype "bidirectional"))
      (node (ref "S1") (pin "SIG11") (pinfunction "SIG2_SIG11") (pintype "bidirectional"))
      (node (ref "S1") (pin "SIG13") (pinfunction "SIG2_SIG13") (pintype "bidirectional"))
      (node (ref "S1") (pin "SIG15") (pinfunction "SIG2_SIG15") (pintype "bidirectional"))
      (node (ref "S1") (pin "SIG17") (pinfunction "SIG2_SIG17") (pintype "bidirectional"))
      (node (ref "S1") (pin "SIG19") (pinfunction "SIG2_SIG19") (pintype "bidirectional"))
      (node (ref "S1") (pin "SIG21") (pinfunction "SIG2_SIG21") (pintype "bidirectional"))
      (node (ref "S1") (pin "SIG23") (pinfunction "SIG2_SIG23") (pintype "bidirectional"))
      (node (ref "S1") (pin "SIG25") (pinfunction "SIG2_SIG25") (pintype "bidirectional"))
      (node (ref "S1") (pin "SIG27") (pinfunction "SIG2_SIG27") (pintype "bidirectional"))
      (node (ref "S1") (pin "SIG29") (pinfunction "SIG2_SIG29") (pintype "bidirectional"))
      (node (ref "S1") (pin "SIG3") (pinfunction "SIG2_SIG3") (pintype "bidirectional"))
      (node (ref "S1") (pin "SIG31") (pinfunction "SIG2_SIG31") (pintype "bidirectional"))
      (node (ref "S1") (pin "SIG5") (pinfunction "SIG2_SIG5") (pintype "bidirectional"))
      (node (ref "S1") (pin "SIG7") (pinfunction "SIG2_SIG7") (pintype "bidirectional"))
      (node (ref "S1") (pin "SIG9") (pinfunction "SIG2_SIG9") (pintype "bidirectional"))
    )
    (net (code "25") (name "/INT") (class "Default")
      (node (ref "IC1") (pin "30") (pinfunction "PD0(RXD/PCINT16)_30") (pintype "bidirectional"))
      (node (ref "PAD67") (pin "1") (pinfunction "P_1") (pintype "passive"))
      (node (ref "PAD68") (pin "1") (pinfunction "P_1") (pintype "passive"))
      (node (ref "PAD69") (pin "1") (pinfunction "P_1") (pintype "passive"))
      (node (ref "PAD70") (pin "1") (pinfunction "P_1") (pintype "passive"))
      (node (ref "PAD71") (pin "1") (pinfunction "P_1") (pintype "passive"))
      (node (ref "PAD72") (pin "1") (pinfunction "P_1") (pintype "passive"))
      (node (ref "PAD92") (pin "1") (pinfunction "P_1") (pintype "passive"))
    )
    (net (code "26") (name "/N$1") (class "Default")
      (node (ref "PAD86") (pin "1") (pinfunction "P_1") (pintype "passive"))
    )
    (net (code "27") (name "/N$2") (class "Default")
      (node (ref "PAD97") (pin "1") (pinfunction "P_1") (pintype "passive"))
      (node (ref "R3") (pin "2") (pinfunction "2_2") (pintype "passive"))
    )
    (net (code "28") (name "/N$3") (class "Default")
      (node (ref "PAD19") (pin "1") (pinfunction "P_1") (pintype "passive"))
      (node (ref "PAD39") (pin "1") (pinfunction "P_1") (pintype "passive"))
    )
    (net (code "29") (name "/N$4") (class "Default")
      (node (ref "PAD20") (pin "1") (pinfunction "P_1") (pintype "passive"))
      (node (ref "PAD40") (pin "1") (pinfunction "P_1") (pintype "passive"))
    )
    (net (code "30") (name "/N$5") (class "Default")
      (node (ref "PAD21") (pin "1") (pinfunction "P_1") (pintype "passive"))
      (node (ref "PAD41") (pin "1") (pinfunction "P_1") (pintype "passive"))
    )
    (net (code "31") (name "/N$6") (class "Default")
      (node (ref "PAD22") (pin "1") (pinfunction "P_1") (pintype "passive"))
      (node (ref "PAD42") (pin "1") (pinfunction "P_1") (pintype "passive"))
    )
    (net (code "32") (name "/N$8") (class "Default")
      (node (ref "PAD43") (pin "1") (pinfunction "P_1") (pintype "passive"))
    )
    (net (code "33") (name "/N$10") (class "Default")
      (node (ref "PAD99") (pin "1") (pinfunction "P_1") (pintype "passive"))
    )
    (net (code "34") (name "/N$12") (class "Default")
      (node (ref "PAD47") (pin "1") (pinfunction "P_1") (pintype "passive"))
    )
    (net (code "35") (name "/N$17") (class "Default")
      (node (ref "PAD98") (pin "1") (pinfunction "P_1") (pintype "passive"))
      (node (ref "R4") (pin "2") (pinfunction "2_2") (pintype "passive"))
    )
    (net (code "36") (name "/N$20") (class "Default")
      (node (ref "PAD79") (pin "1") (pinfunction "P_1") (pintype "passive"))
    )
    (net (code "37") (name "/RESET") (class "Default")
      (node (ref "IC1") (pin "29") (pinfunction "PC6(/RESET/PCINT14)_29") (pintype "bidirectional"))
      (node (ref "PAD88") (pin "1") (pinfunction "P_1") (pintype "passive"))
    )
    (net (code "38") (name "/SCL") (class "Default")
      (node (ref "IC1") (pin "28") (pinfunction "PC5(ADC5/SCL/PCINT13)_28") (pintype "bidirectional"))
      (node (ref "PAD51") (pin "1") (pinfunction "P_1") (pintype "passive"))
      (node (ref "PAD56") (pin "1") (pinfunction "P_1") (pintype "passive"))
      (node (ref "PAD60") (pin "1") (pinfunction "P_1") (pintype "passive"))
      (node (ref "PAD64") (pin "1") (pinfunction "P_1") (pintype "passive"))
      (node (ref "PAD73") (pin "1") (pinfunction "P_1") (pintype "passive"))
      (node (ref "PAD82") (pin "1") (pinfunction "P_1") (pintype "passive"))
      (node (ref "PAD91") (pin "1") (pinfunction "P_1") (pintype "passive"))
      (node (ref "R1") (pin "1") (pinfunction "1_1") (pintype "passive"))
    )
    (net (code "39") (name "/SDA") (class "Default")
      (node (ref "IC1") (pin "27") (pinfunction "PC4(ADC4/SDA/PCINT12)_27") (pintype "bidirectional"))
      (node (ref "PAD52") (pin "1") (pinfunction "P_1") (pintype "passive"))
      (node (ref "PAD55") (pin "1") (pinfunction "P_1") (pintype "passive"))
      (node (ref "PAD59") (pin "1") (pinfunction "P_1") (pintype "passive"))
      (node (ref "PAD63") (pin "1") (pinfunction "P_1") (pintype "passive"))
      (node (ref "PAD74") (pin "1") (pinfunction "P_1") (pintype "passive"))
      (node (ref "PAD81") (pin "1") (pinfunction "P_1") (pintype "passive"))
      (node (ref "PAD90") (pin "1") (pinfunction "P_1") (pintype "passive"))
      (node (ref "R2") (pin "1") (pinfunction "1_1") (pintype "passive"))
    )
    (net (code "40") (name "/VCC") (class "Default")
      (node (ref "C1") (pin "1") (pinfunction "1_1") (pintype "passive"))
      (node (ref "C10") (pin "1") (pinfunction "1_1") (pintype "passive"))
      (node (ref "C11") (pin "1") (pinfunction "1_1") (pintype "passive"))
      (node (ref "C12") (pin "1") (pinfunction "1_1") (pintype "passive"))
      (node (ref "C13") (pin "1") (pinfunction "1_1") (pintype "passive"))
      (node (ref "C14") (pin "1") (pinfunction "1_1") (pintype "passive"))
      (node (ref "C15") (pin "1") (pinfunction "1_1") (pintype "passive"))
      (node (ref "C16") (pin "1") (pinfunction "1_1") (pintype "passive"))
      (node (ref "C17") (pin "1") (pinfunction "1_1") (pintype "passive"))
      (node (ref "C18") (pin "1") (pinfunction "1_1") (pintype "passive"))
      (node (ref "C19") (pin "1") (pinfunction "1_1") (pintype "passive"))
      (node (ref "C2") (pin "1") (pinfunction "1_1") (pintype "passive"))
      (node (ref "C5") (pin "1") (pinfunction "1_1") (pintype "passive"))
      (node (ref "C6") (pin "1") (pinfunction "1_1") (pintype "passive"))
      (node (ref "C7") (pin "1") (pinfunction "1_1") (pintype "passive"))
      (node (ref "C8") (pin "1") (pinfunction "1_1") (pintype "passive"))
      (node (ref "C9") (pin "1") (pinfunction "1_1") (pintype "passive"))
      (node (ref "IC1") (pin "18") (pinfunction "AVCC_18") (pintype "passive"))
      (node (ref "IC1") (pin "20") (pinfunction "AREF_20") (pintype "passive"))
      (node (ref "IC1") (pin "4") (pinfunction "VCC_4") (pintype "power_in"))
      (node (ref "IC1") (pin "6") (pinfunction "VCC_6") (pintype "power_in"))
      (node (ref "IC2") (pin "2") (pinfunction "VOUT_2") (pintype "output"))
      (node (ref "IC2") (pin "3") (pinfunction "VIN_3") (pintype "input"))
      (node (ref "LED1") (pin "1-VDD") (pinfunction "VDD_1-VDD") (pintype "power_in"))
      (node (ref "LED10") (pin "1-VDD") (pinfunction "VDD_1-VDD") (pintype "power_in"))
      (node (ref "LED11") (pin "1-VDD") (pinfunction "VDD_1-VDD") (pintype "power_in"))
      (node (ref "LED12") (pin "1-VDD") (pinfunction "VDD_1-VDD") (pintype "power_in"))
      (node (ref "LED13") (pin "1-VDD") (pinfunction "VDD_1-VDD") (pintype "power_in"))
      (node (ref "LED14") (pin "1-VDD") (pinfunction "VDD_1-VDD") (pintype "power_in"))
      (node (ref "LED15") (pin "1-VDD") (pinfunction "VDD_1-VDD") (pintype "power_in"))
      (node (ref "LED16") (pin "1-VDD") (pinfunction "VDD_1-VDD") (pintype "power_in"))
      (node (ref "LED2") (pin "1-VDD") (pinfunction "VDD_1-VDD") (pintype "power_in"))
      (node (ref "LED3") (pin "1-VDD") (pinfunction "VDD_1-VDD") (pintype "power_in"))
      (node (ref "LED4") (pin "1-VDD") (pinfunction "VDD_1-VDD") (pintype "power_in"))
      (node (ref "LED5") (pin "1-VDD") (pinfunction "VDD_1-VDD") (pintype "power_in"))
      (node (ref "LED6") (pin "1-VDD") (pinfunction "VDD_1-VDD") (pintype "power_in"))
      (node (ref "LED7") (pin "1-VDD") (pinfunction "VDD_1-VDD") (pintype "power_in"))
      (node (ref "LED8") (pin "1-VDD") (pinfunction "VDD_1-VDD") (pintype "power_in"))
      (node (ref "LED9") (pin "1-VDD") (pinfunction "VDD_1-VDD") (pintype "power_in"))
      (node (ref "PAD104") (pin "1") (pinfunction "P_1") (pintype "passive"))
      (node (ref "PAD46") (pin "1") (pinfunction "P_1") (pintype "passive"))
      (node (ref "PAD48") (pin "1") (pinfunction "P_1") (pintype "passive"))
      (node (ref "PAD49") (pin "1") (pinfunction "P_1") (pintype "passive"))
      (node (ref "PAD54") (pin "1") (pinfunction "P_1") (pintype "passive"))
      (node (ref "PAD57") (pin "1") (pinfunction "P_1") (pintype "passive"))
      (node (ref "PAD62") (pin "1") (pinfunction "P_1") (pintype "passive"))
      (node (ref "PAD66") (pin "1") (pinfunction "P_1") (pintype "passive"))
      (node (ref "PAD76") (pin "1") (pinfunction "P_1") (pintype "passive"))
      (node (ref "PAD83") (pin "1") (pinfunction "P_1") (pintype "passive"))
      (node (ref "PAD94") (pin "1") (pinfunction "P_1") (pintype "passive"))
      (node (ref "PAD96") (pin "1") (pinfunction "P_1") (pintype "passive"))
    )
    (net (code "41") (name "/XTAL1") (class "Default")
      (node (ref "C4") (pin "2") (pinfunction "2_2") (pintype "passive"))
      (node (ref "IC1") (pin "7") (pinfunction "PB6(XTAL1/TOSC1/PCINT6)_7") (pintype "bidirectional"))
      (node (ref "X1") (pin "2") (pinfunction "2_2") (pintype "passive"))
    )
    (net (code "42") (name "/XTAL2") (class "Default")
      (node (ref "C3") (pin "2") (pinfunction "2_2") (pintype "passive"))
      (node (ref "IC1") (pin "8") (pinfunction "PB7(XTAL2/TOSC2/PCINT7)_8") (pintype "bidirectional"))
      (node (ref "X1") (pin "1") (pinfunction "1_1") (pintype "passive"))
    )
    (net (code "43") (name "Net-(LED1-DO)") (class "Default")
      (node (ref "LED1") (pin "2-DOUT") (pinfunction "DO_2-DOUT") (pintype "output"))
      (node (ref "LED2") (pin "4-DIN") (pinfunction "DI_4-DIN") (pintype "input"))
    )
    (net (code "44") (name "Net-(LED2-DO)") (class "Default")
      (node (ref "LED2") (pin "2-DOUT") (pinfunction "DO_2-DOUT") (pintype "output"))
      (node (ref "LED3") (pin "4-DIN") (pinfunction "DI_4-DIN") (pintype "input"))
    )
    (net (code "45") (name "Net-(LED3-DO)") (class "Default")
      (node (ref "LED3") (pin "2-DOUT") (pinfunction "DO_2-DOUT") (pintype "output"))
      (node (ref "LED4") (pin "4-DIN") (pinfunction "DI_4-DIN") (pintype "input"))
    )
    (net (code "46") (name "Net-(LED5-DO)") (class "Default")
      (node (ref "LED5") (pin "2-DOUT") (pinfunction "DO_2-DOUT") (pintype "output"))
      (node (ref "LED6") (pin "4-DIN") (pinfunction "DI_4-DIN") (pintype "input"))
    )
    (net (code "47") (name "Net-(LED6-DO)") (class "Default")
      (node (ref "LED6") (pin "2-DOUT") (pinfunction "DO_2-DOUT") (pintype "output"))
      (node (ref "LED7") (pin "4-DIN") (pinfunction "DI_4-DIN") (pintype "input"))
    )
    (net (code "48") (name "Net-(LED7-DO)") (class "Default")
      (node (ref "LED7") (pin "2-DOUT") (pinfunction "DO_2-DOUT") (pintype "output"))
      (node (ref "LED8") (pin "4-DIN") (pinfunction "DI_4-DIN") (pintype "input"))
    )
    (net (code "49") (name "Net-(LED10-DI)") (class "Default")
      (node (ref "LED10") (pin "4-DIN") (pinfunction "DI_4-DIN") (pintype "input"))
      (node (ref "LED9") (pin "2-DOUT") (pinfunction "DO_2-DOUT") (pintype "output"))
    )
    (net (code "50") (name "Net-(LED10-DO)") (class "Default")
      (node (ref "LED10") (pin "2-DOUT") (pinfunction "DO_2-DOUT") (pintype "output"))
      (node (ref "LED11") (pin "4-DIN") (pinfunction "DI_4-DIN") (pintype "input"))
      (node (ref "PAD106") (pin "1") (pinfunction "P_1") (pintype "passive"))
      (node (ref "PAD107") (pin "1") (pinfunction "P_1") (pintype "passive"))
    )
    (net (code "51") (name "Net-(LED11-DO)") (class "Default")
      (node (ref "LED11") (pin "2-DOUT") (pinfunction "DO_2-DOUT") (pintype "output"))
      (node (ref "LED12") (pin "4-DIN") (pinfunction "DI_4-DIN") (pintype "input"))
    )
    (net (code "52") (name "Net-(LED13-DO)") (class "Default")
      (node (ref "LED13") (pin "2-DOUT") (pinfunction "DO_2-DOUT") (pintype "output"))
      (node (ref "LED14") (pin "4-DIN") (pinfunction "DI_4-DIN") (pintype "input"))
    )
    (net (code "53") (name "Net-(LED14-DO)") (class "Default")
      (node (ref "LED14") (pin "2-DOUT") (pinfunction "DO_2-DOUT") (pintype "output"))
      (node (ref "LED15") (pin "4-DIN") (pinfunction "DI_4-DIN") (pintype "input"))
      (node (ref "PAD108") (pin "1") (pinfunction "P_1") (pintype "passive"))
      (node (ref "PAD109") (pin "1") (pinfunction "P_1") (pintype "passive"))
    )
    (net (code "54") (name "Net-(LED15-DO)") (class "Default")
      (node (ref "LED15") (pin "2-DOUT") (pinfunction "DO_2-DOUT") (pintype "output"))
      (node (ref "LED16") (pin "4-DIN") (pinfunction "DI_4-DIN") (pintype "input"))
    )
    (net (code "55") (name "unconnected-(PAD14-P-Pad1)") (class "Default")
      (node (ref "PAD14") (pin "1") (pinfunction "P_1") (pintype "passive"))
    )
    (net (code "56") (name "unconnected-(PAD77-P-Pad1)") (class "Default")
      (node (ref "PAD77") (pin "1") (pinfunction "P_1") (pintype "passive"))
    )
    (net (code "57") (name "unconnected-(PAD78-P-Pad1)") (class "Default")
      (node (ref "PAD78") (pin "1") (pinfunction "P_1") (pintype "passive"))
    )
    (net (code "58") (name "unconnected-(PAD80-P-Pad1)") (class "Default")
      (node (ref "PAD80") (pin "1") (pinfunction "P_1") (pintype "passive"))
    )
    (net (code "59") (name "unconnected-(PAD84-P-Pad1)") (class "Default")
      (node (ref "PAD84") (pin "1") (pinfunction "P_1") (pintype "passive"))
    )
    (net (code "60") (name "unconnected-(PAD85-P-Pad1)") (class "Default")
      (node (ref "PAD85") (pin "1") (pinfunction "P_1") (pintype "passive"))
    )
  )
)
